# SCH-Power.net
KiCad netlist of a schematic drawn in Altium Designer
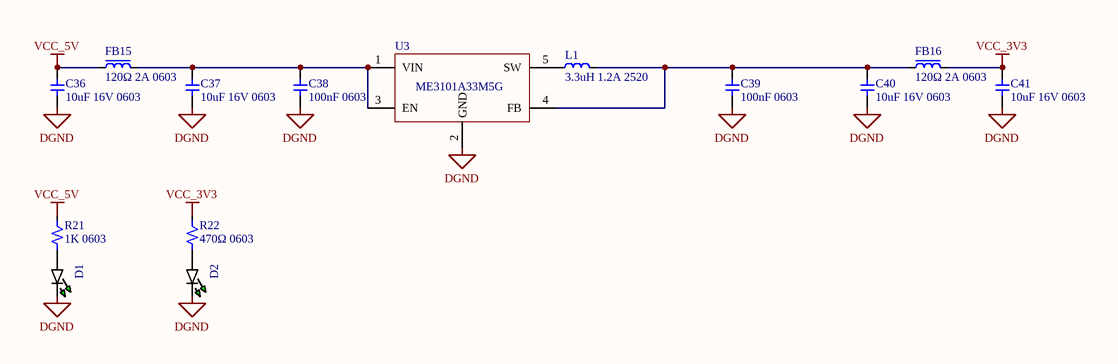
[diagram p0: SCH-Power.SchDoc]

(export (version "E")
  (design (tool "Eeschema 10.0.6"))
  (components
    (comp (ref "C36")
      (value "10uF 16V 0603")
      (footprint "CAPC1608X08 (0603)")
      (description "贴片MLCC电容 10uF 16V X5R 20% 0603")
      (fields (field (name "1ST PARTNUMBER") "CC0603KRX5R7BB106"))
      (libsource (lib "12-无源器件") (part "10uF 16V 0603"))
    )
    (comp (ref "C37")
      (value "10uF 16V 0603")
      (footprint "CAPC1608X08 (0603)")
      (description "贴片MLCC电容 10uF 16V X5R 20% 0603")
      (fields (field (name "1ST PARTNUMBER") "CC0603KRX5R7BB106"))
      (libsource (lib "12-无源器件") (part "10uF 16V 0603"))
    )
    (comp (ref "C38")
      (value "100nF 0603")
      (footprint "CAPC1608X08 (0603)")
      (description "贴片MLCC电容 100nF 50V X7R 10% 0603")
      (fields
        (field (name "1ST PARTNUMBER") "CC0603KRX7R9BB104")
        (field (name "2ND PARTNUMBER") "CGA3E2X7R1H104K080AA")
      )
      (libsource (lib "12-无源器件") (part "100nF 0603"))
    )
    (comp (ref "C39")
      (value "100nF 0603")
      (footprint "CAPC1608X08 (0603)")
      (description "贴片MLCC电容 100nF 50V X7R 10% 0603")
      (fields
        (field (name "1ST PARTNUMBER") "CC0603KRX7R9BB104")
        (field (name "2ND PARTNUMBER") "CGA3E2X7R1H104K080AA")
      )
      (libsource (lib "12-无源器件") (part "100nF 0603"))
    )
    (comp (ref "C40")
      (value "10uF 16V 0603")
      (footprint "CAPC1608X08 (0603)")
      (description "贴片MLCC电容 10uF 16V X5R 20% 0603")
      (fields (field (name "1ST PARTNUMBER") "CC0603KRX5R7BB106"))
      (libsource (lib "12-无源器件") (part "10uF 16V 0603"))
    )
    (comp (ref "C41")
      (value "10uF 16V 0603")
      (footprint "CAPC1608X08 (0603)")
      (description "贴片MLCC电容 10uF 16V X5R 20% 0603")
      (fields (field (name "1ST PARTNUMBER") "CC0603KRX5R7BB106"))
      (libsource (lib "12-无源器件") (part "10uF 16V 0603"))
    )
    (comp (ref "D1")
      (value "GR/0603")
      (footprint "DIOC1608X06N-(0603)")
      (description "标准LED-SMD Green Clear 569nm")
      (fields (field (name "1ST PARTNUMBER") "LTST-C190GKT") (field (name "2ND PARTNUMBER") "可国产替代"))
      (libsource (lib "14-光电器件") (part "GR/0603"))
    )
    (comp (ref "D2")
      (value "GR/0603")
      (footprint "DIOC1608X06N-(0603)")
      (description "标准LED-SMD Green Clear 569nm")
      (fields (field (name "1ST PARTNUMBER") "LTST-C190GKT") (field (name "2ND PARTNUMBER") "可国产替代"))
      (libsource (lib "14-光电器件") (part "GR/0603"))
    )
    (comp (ref "FB15")
      (value "120Ω 2A 0603")
      (footprint "INDC1608X08 (0603)")
      (description "电源线磁珠 0603 120Ω@100MHz 2A")
      (fields
        (field (name "1ST PARTNUMBER") "PZ1608U121-2R0TF")
        (field (name "2ND PARTNUMBER") "BLM18PG121SN1D")
      )
      (libsource (lib "12-无源器件") (part "120Ω@100MHz 2A 0603"))
    )
    (comp (ref "FB16")
      (value "120Ω 2A 0603")
      (footprint "INDC1608X08 (0603)")
      (description "电源线磁珠 0603 120Ω@100MHz 2A")
      (fields
        (field (name "1ST PARTNUMBER") "PZ1608U121-2R0TF")
        (field (name "2ND PARTNUMBER") "BLM18PG121SN1D")
      )
      (libsource (lib "12-无源器件") (part "120Ω@100MHz 2A 0603"))
    )
    (comp (ref "L1")
      (value "3.3uH 1.2A 2520")
      (footprint "INDC2520X10N-(2520)")
      (description "叠片电感 2520 3.3uH 1.2A ±20%")
      (fields (field (name "1ST PARTNUMBER") "MPL2520S3R3MHT"))
      (libsource (lib "12-无源器件") (part "3.3uH 1.2A 2520"))
    )
    (comp (ref "R21")
      (value "1K 0603")
      (footprint "RESC1608X04 (0603)")
      (description "贴片厚膜电阻 1kΩ 1% 0603")
      (fields
        (field (name "1ST PARTNUMBER") "RC0603FR-071KL")
        (field (name "2ND PARTNUMBER") "CR0603-FX-1001ELF")
      )
      (libsource (lib "12-无源器件") (part "1K 0603"))
    )
    (comp (ref "R22")
      (value "470Ω 0603")
      (footprint "RESC1608X04 (0603)")
      (description "贴片厚膜电阻 470Ω 1% 0603")
      (fields
        (field (name "1ST PARTNUMBER") "RC0603FR-07470RL")
        (field (name "2ND PARTNUMBER") "CR0603-FX-4700ELF")
      )
      (libsource (lib "12-无源器件") (part "470Ω 0603"))
    )
    (comp (ref "U3")
      (value "ME3101A33M5G")
      (footprint "SOT95P280X145-5N")
      (description "6.5Vin, 3.3Vout, 500mA 同步降压转换器")
      (fields
        (field (name "2ND PARTNUMBER") "LM3671MFX-3.3/NOPB")
        (field (name "1ST PARTNUMBER") "ME3101A33M5G")
      )
      (libsource (lib "11-半导体") (part "ME3101A33M5G"))
    )
  )
  (nets
    (net (code "1") (name "DGND") (class "Default")
      (node (ref "C36") (pin "2") (pinfunction "2_2") (pintype "passive"))
      (node (ref "C37") (pin "2") (pinfunction "2_2") (pintype "passive"))
      (node (ref "C38") (pin "2") (pinfunction "2_2") (pintype "passive"))
      (node (ref "C39") (pin "2") (pinfunction "2_2") (pintype "passive"))
      (node (ref "C40") (pin "2") (pinfunction "2_2") (pintype "passive"))
      (node (ref "C41") (pin "2") (pinfunction "2_2") (pintype "passive"))
      (node (ref "D1") (pin "1") (pinfunction "A_1") (pintype "passive"))
      (node (ref "D2") (pin "1") (pinfunction "A_1") (pintype "passive"))
      (node (ref "U3") (pin "2") (pinfunction "GND_2") (pintype "power_in"))
    )
    (net (code "2") (name "Net-(D1-K)") (class "Default")
      (node (ref "D1") (pin "2") (pinfunction "K_2") (pintype "passive"))
      (node (ref "R21") (pin "1") (pinfunction "1_1") (pintype "passive"))
    )
    (net (code "3") (name "Net-(D2-K)") (class "Default")
      (node (ref "D2") (pin "2") (pinfunction "K_2") (pintype "passive"))
      (node (ref "R22") (pin "1") (pinfunction "1_1") (pintype "passive"))
    )
    (net (code "4") (name "Net-(U3-EN)") (class "Default")
      (node (ref "C37") (pin "1") (pinfunction "1_1") (pintype "passive"))
      (node (ref "C38") (pin "1") (pinfunction "1_1") (pintype "passive"))
      (node (ref "FB15") (pin "2") (pinfunction "2_2") (pintype "passive"))
      (node (ref "U3") (pin "1") (pinfunction "VIN_1") (pintype "power_in"))
      (node (ref "U3") (pin "3") (pinfunction "EN_3") (pintype "passive"))
    )
    (net (code "5") (name "Net-(U3-FB)") (class "Default")
      (node (ref "C39") (pin "1") (pinfunction "1_1") (pintype "passive"))
      (node (ref "C40") (pin "1") (pinfunction "1_1") (pintype "passive"))
      (node (ref "FB16") (pin "1") (pinfunction "1_1") (pintype "passive"))
      (node (ref "L1") (pin "2") (pinfunction "2_2") (pintype "passive"))
      (node (ref "U3") (pin "4") (pinfunction "FB_4") (pintype "passive"))
    )
    (net (code "6") (name "Net-(U3-SW)") (class "Default")
      (node (ref "L1") (pin "1") (pinfunction "1_1") (pintype "passive"))
      (node (ref "U3") (pin "5") (pinfunction "SW_5") (pintype "power_in"))
    )
    (net (code "7") (name "VCC_3V3") (class "Default")
      (node (ref "C41") (pin "1") (pinfunction "1_1") (pintype "passive"))
      (node (ref "FB16") (pin "2") (pinfunction "2_2") (pintype "passive"))
      (node (ref "R22") (pin "2") (pinfunction "2_2") (pintype "passive"))
    )
    (net (code "8") (name "VCC_5V") (class "Default")
      (node (ref "C36") (pin "1") (pinfunction "1_1") (pintype "passive"))
      (node (ref "FB15") (pin "1") (pinfunction "1_1") (pintype "passive"))
      (node (ref "R21") (pin "2") (pinfunction "2_2") (pintype "passive"))
    )
  )
)
